# 01-MCU-V2_3.net
KiCad netlist of a schematic drawn in Altium Designer
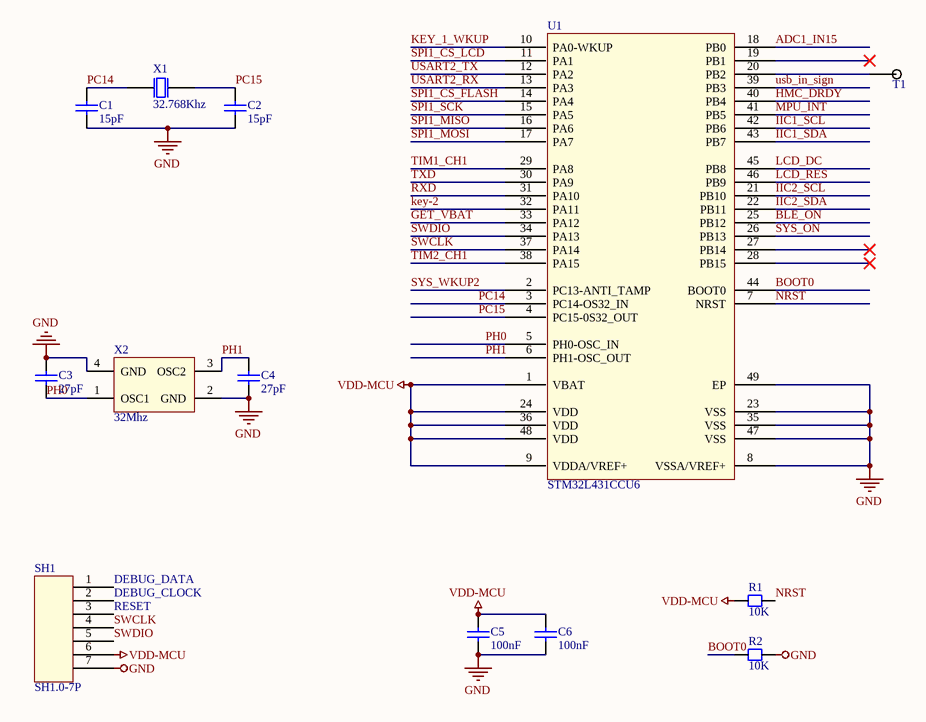
[diagram p0: 01-MCU-V2.3.SchDoc]

(export (version "E")
  (design (tool "Eeschema 10.0.6"))
  (components
    (comp (ref "C1")
      (value "15pF")
      (footprint "CC1005-0402")
      (description "贴片电容")
      (libsource (lib "tianxiaohua_Schlib") (part "Chip capacitor"))
    )
    (comp (ref "C2")
      (value "15pF")
      (footprint "CC1005-0402")
      (description "贴片电容")
      (libsource (lib "tianxiaohua_Schlib") (part "Chip capacitor"))
    )
    (comp (ref "C3")
      (value "27pF")
      (footprint "CC1005-0402")
      (description "贴片电容")
      (libsource (lib "tianxiaohua_Schlib") (part "Chip capacitor"))
    )
    (comp (ref "C4")
      (value "27pF")
      (footprint "CC1005-0402")
      (description "贴片电容")
      (libsource (lib "tianxiaohua_Schlib") (part "Chip capacitor"))
    )
    (comp (ref "C5")
      (value "100nF")
      (footprint "CC1005-0402")
      (description "贴片电容")
      (libsource (lib "tianxiaohua_Schlib") (part "Chip capacitor"))
    )
    (comp (ref "C6")
      (value "100nF")
      (footprint "CC1005-0402")
      (description "贴片电容")
      (libsource (lib "tianxiaohua_Schlib") (part "Chip capacitor"))
    )
    (comp (ref "R1")
      (value "10K")
      (footprint "CR1005-0402")
      (description "贴片电阻")
      (libsource (lib "tianxiaohua_Schlib") (part "Chip resistor"))
    )
    (comp (ref "R2")
      (value "10K")
      (footprint "CR1005-0402")
      (description "贴片电阻")
      (libsource (lib "tianxiaohua_Schlib") (part "Chip resistor"))
    )
    (comp (ref "SH1")
      (value "SH1.0-7P")
      (footprint "SH1.0-7P")
      (description "间距为1mm的端子")
      (libsource (lib "tianxiaohua_Schlib") (part "SH1.0-7P"))
    )
    (comp (ref "T1") (value "测试点") (footprint "测试点") (libsource (lib "tianxiaohua_Schlib") (part "测试点")))
    (comp (ref "U1")
      (value "STM32L431CCU6")
      (footprint "STM32-UFQFPN48_N")
      (description "stm32低功耗单片机 主频80MHz")
      (libsource (lib "tianxiaohua_Schlib") (part "STM32L431CCU6"))
    )
    (comp (ref "X1")
      (value "32.768Khz")
      (footprint "XTAL-2012")
      (description "2012封装的时钟晶振")
      (libsource (lib "tianxiaohua_Schlib") (part "XTAL 2012"))
    )
    (comp (ref "X2")
      (value "32Mhz")
      (footprint "XTAL-2016")
      (description "2016封装的晶振")
      (libsource (lib "tianxiaohua_Schlib") (part "XTAL 2016"))
    )
  )
  (nets
    (net (code "1") (name "/ADC1_IN15") (class "Default")
      (node (ref "U1") (pin "18") (pinfunction "PB0_18") (pintype "passive"))
    )
    (net (code "2") (name "/BLE_ON") (class "Default")
      (node (ref "U1") (pin "25") (pinfunction "PB12_25") (pintype "passive"))
    )
    (net (code "3") (name "/BOOT0") (class "Default")
      (node (ref "R2") (pin "2") (pinfunction "2_2") (pintype "passive"))
      (node (ref "U1") (pin "44") (pinfunction "BOOT0_44") (pintype "passive"))
    )
    (net (code "4") (name "/DEBUG_CLOCK") (class "Default")
      (node (ref "SH1") (pin "2") (pinfunction "2_2") (pintype "passive"))
    )
    (net (code "5") (name "/DEBUG_DATA") (class "Default") (node (ref "SH1") (pin "1") (pintype "passive")))
    (net (code "6") (name "/GET_VBAT") (class "Default")
      (node (ref "U1") (pin "33") (pinfunction "PA12_33") (pintype "passive"))
    )
    (net (code "7") (name "/HMC_DRDY") (class "Default")
      (node (ref "U1") (pin "40") (pinfunction "PB4_40") (pintype "passive"))
    )
    (net (code "8") (name "/IIC1_SCL") (class "Default")
      (node (ref "U1") (pin "42") (pinfunction "PB6_42") (pintype "passive"))
    )
    (net (code "9") (name "/IIC1_SDA") (class "Default")
      (node (ref "U1") (pin "43") (pinfunction "PB7_43") (pintype "passive"))
    )
    (net (code "10") (name "/IIC2_SCL") (class "Default")
      (node (ref "U1") (pin "21") (pinfunction "PB10_21") (pintype "passive"))
    )
    (net (code "11") (name "/IIC2_SDA") (class "Default")
      (node (ref "U1") (pin "22") (pinfunction "PB11_22") (pintype "passive"))
    )
    (net (code "12") (name "/KEY_1_WKUP") (class "Default")
      (node (ref "U1") (pin "10") (pinfunction "PA0-WKUP_10") (pintype "passive"))
    )
    (net (code "13") (name "/LCD_DC") (class "Default")
      (node (ref "U1") (pin "45") (pinfunction "PB8_45") (pintype "passive"))
    )
    (net (code "14") (name "/LCD_RES") (class "Default")
      (node (ref "U1") (pin "46") (pinfunction "PB9_46") (pintype "passive"))
    )
    (net (code "15") (name "/MPU_INT") (class "Default")
      (node (ref "U1") (pin "41") (pinfunction "PB5_41") (pintype "passive"))
    )
    (net (code "16") (name "/NRST") (class "Default")
      (node (ref "R1") (pin "1") (pinfunction "1_1") (pintype "passive"))
      (node (ref "U1") (pin "7") (pinfunction "NRST_7") (pintype "passive"))
    )
    (net (code "17") (name "/PC14") (class "Default")
      (node (ref "C1") (pin "2") (pinfunction "2_2") (pintype "passive"))
      (node (ref "U1") (pin "3") (pinfunction "PC14-OS32_IN_3") (pintype "passive"))
      (node (ref "X1") (pin "2") (pinfunction "2_2") (pintype "passive"))
    )
    (net (code "18") (name "/PC15") (class "Default")
      (node (ref "C2") (pin "2") (pinfunction "2_2") (pintype "passive"))
      (node (ref "U1") (pin "4") (pinfunction "PC15-0S32_OUT_4") (pintype "passive"))
      (node (ref "X1") (pin "1") (pinfunction "1_1") (pintype "passive"))
    )
    (net (code "19") (name "/PH0") (class "Default")
      (node (ref "C3") (pin "1") (pinfunction "1_1") (pintype "passive"))
      (node (ref "U1") (pin "5") (pinfunction "PH0-OSC_IN_5") (pintype "passive"))
      (node (ref "X2") (pin "1") (pinfunction "OSC1_1") (pintype "passive"))
    )
    (net (code "20") (name "/PH1") (class "Default")
      (node (ref "C4") (pin "2") (pinfunction "2_2") (pintype "passive"))
      (node (ref "U1") (pin "6") (pinfunction "PH1-OSC_OUT_6") (pintype "passive"))
      (node (ref "X2") (pin "3") (pinfunction "OSC2_3") (pintype "passive"))
    )
    (net (code "21") (name "/RESET") (class "Default") (node (ref "SH1") (pin "3") (pintype "passive")))
    (net (code "22") (name "/RXD") (class "Default")
      (node (ref "U1") (pin "31") (pinfunction "PA10_31") (pintype "passive"))
    )
    (net (code "23") (name "/SPI1_CS_FLASH") (class "Default")
      (node (ref "U1") (pin "14") (pinfunction "PA4_14") (pintype "passive"))
    )
    (net (code "24") (name "/SPI1_CS_LCD") (class "Default")
      (node (ref "U1") (pin "11") (pinfunction "PA1_11") (pintype "passive"))
    )
    (net (code "25") (name "/SPI1_MISO") (class "Default")
      (node (ref "U1") (pin "16") (pinfunction "PA6_16") (pintype "passive"))
    )
    (net (code "26") (name "/SPI1_MOSI") (class "Default")
      (node (ref "U1") (pin "17") (pinfunction "PA7_17") (pintype "passive"))
    )
    (net (code "27") (name "/SPI1_SCK") (class "Default")
      (node (ref "U1") (pin "15") (pinfunction "PA5_15") (pintype "passive"))
    )
    (net (code "28") (name "/SWCLK") (class "Default")
      (node (ref "SH1") (pin "4") (pinfunction "4_4") (pintype "passive"))
      (node (ref "U1") (pin "37") (pinfunction "PA14_37") (pintype "passive"))
    )
    (net (code "29") (name "/SWDIO") (class "Default")
      (node (ref "SH1") (pin "5") (pintype "passive"))
      (node (ref "U1") (pin "34") (pinfunction "PA13_34") (pintype "passive"))
    )
    (net (code "30") (name "/SYS_ON") (class "Default")
      (node (ref "U1") (pin "26") (pinfunction "PB13_26") (pintype "passive"))
    )
    (net (code "31") (name "/SYS_WKUP2") (class "Default")
      (node (ref "U1") (pin "2") (pinfunction "PC13-ANTI_TAMP_2") (pintype "passive"))
    )
    (net (code "32") (name "/TIM1_CH1") (class "Default")
      (node (ref "U1") (pin "29") (pinfunction "PA8_29") (pintype "passive"))
    )
    (net (code "33") (name "/TIM2_CH1") (class "Default")
      (node (ref "U1") (pin "38") (pinfunction "PA15_38") (pintype "passive"))
    )
    (net (code "34") (name "/TXD") (class "Default")
      (node (ref "U1") (pin "30") (pinfunction "PA9_30") (pintype "passive"))
    )
    (net (code "35") (name "/USART2_RX") (class "Default")
      (node (ref "U1") (pin "13") (pinfunction "PA3_13") (pintype "passive"))
    )
    (net (code "36") (name "/USART2_TX") (class "Default")
      (node (ref "U1") (pin "12") (pinfunction "PA2_12") (pintype "passive"))
    )
    (net (code "37") (name "/key-2") (class "Default")
      (node (ref "U1") (pin "32") (pinfunction "PA11_32") (pintype "passive"))
    )
    (net (code "38") (name "/usb_in_sign") (class "Default")
      (node (ref "U1") (pin "39") (pinfunction "PB3_39") (pintype "passive"))
    )
    (net (code "39") (name "GND") (class "Default")
      (node (ref "C1") (pin "1") (pinfunction "1_1") (pintype "passive"))
      (node (ref "C2") (pin "1") (pinfunction "1_1") (pintype "passive"))
      (node (ref "C3") (pin "2") (pinfunction "2_2") (pintype "passive"))
      (node (ref "C4") (pin "1") (pinfunction "1_1") (pintype "passive"))
      (node (ref "C5") (pin "1") (pinfunction "1_1") (pintype "passive"))
      (node (ref "C6") (pin "1") (pinfunction "1_1") (pintype "passive"))
      (node (ref "R2") (pin "1") (pinfunction "1_1") (pintype "passive"))
      (node (ref "SH1") (pin "7") (pinfunction "7_7") (pintype "passive"))
      (node (ref "U1") (pin "23") (pinfunction "VSS_23") (pintype "passive"))
      (node (ref "U1") (pin "35") (pinfunction "VSS_35") (pintype "passive"))
      (node (ref "U1") (pin "47") (pinfunction "VSS_47") (pintype "passive"))
      (node (ref "U1") (pin "49") (pinfunction "EP_49") (pintype "passive"))
      (node (ref "U1") (pin "8") (pinfunction "VSSA/VREF+_8") (pintype "passive"))
      (node (ref "X2") (pin "2") (pinfunction "GND_2") (pintype "passive"))
      (node (ref "X2") (pin "4") (pinfunction "GND_4") (pintype "passive"))
    )
    (net (code "40") (name "Net-(U1-PB2)") (class "Default")
      (node (ref "T1") (pin "1") (pinfunction "1_1") (pintype "passive"))
      (node (ref "U1") (pin "20") (pinfunction "PB2_20") (pintype "passive"))
    )
    (net (code "41") (name "VDD-MCU") (class "Default")
      (node (ref "C5") (pin "2") (pinfunction "2_2") (pintype "passive"))
      (node (ref "C6") (pin "2") (pinfunction "2_2") (pintype "passive"))
      (node (ref "R1") (pin "2") (pinfunction "2_2") (pintype "passive"))
      (node (ref "SH1") (pin "6") (pinfunction "6_6") (pintype "passive"))
      (node (ref "U1") (pin "1") (pinfunction "VBAT_1") (pintype "passive"))
      (node (ref "U1") (pin "24") (pinfunction "VDD_24") (pintype "passive"))
      (node (ref "U1") (pin "36") (pinfunction "VDD_36") (pintype "passive"))
      (node (ref "U1") (pin "48") (pinfunction "VDD_48") (pintype "passive"))
      (node (ref "U1") (pin "9") (pinfunction "VDDA/VREF+_9") (pintype "passive"))
    )
    (net (code "42") (name "unconnected-(U1-PB1-Pad19)") (class "Default")
      (node (ref "U1") (pin "19") (pinfunction "PB1_19") (pintype "passive+no_connect"))
    )
    (net (code "43") (name "unconnected-(U1-PB14-Pad27)") (class "Default")
      (node (ref "U1") (pin "27") (pinfunction "PB14_27") (pintype "passive+no_connect"))
    )
    (net (code "44") (name "unconnected-(U1-PB15-Pad28)") (class "Default")
      (node (ref "U1") (pin "28") (pinfunction "PB15_28") (pintype "passive+no_connect"))
    )
  )
)
